# TopLevel.net
KiCad netlist of a schematic drawn in Altium Designer
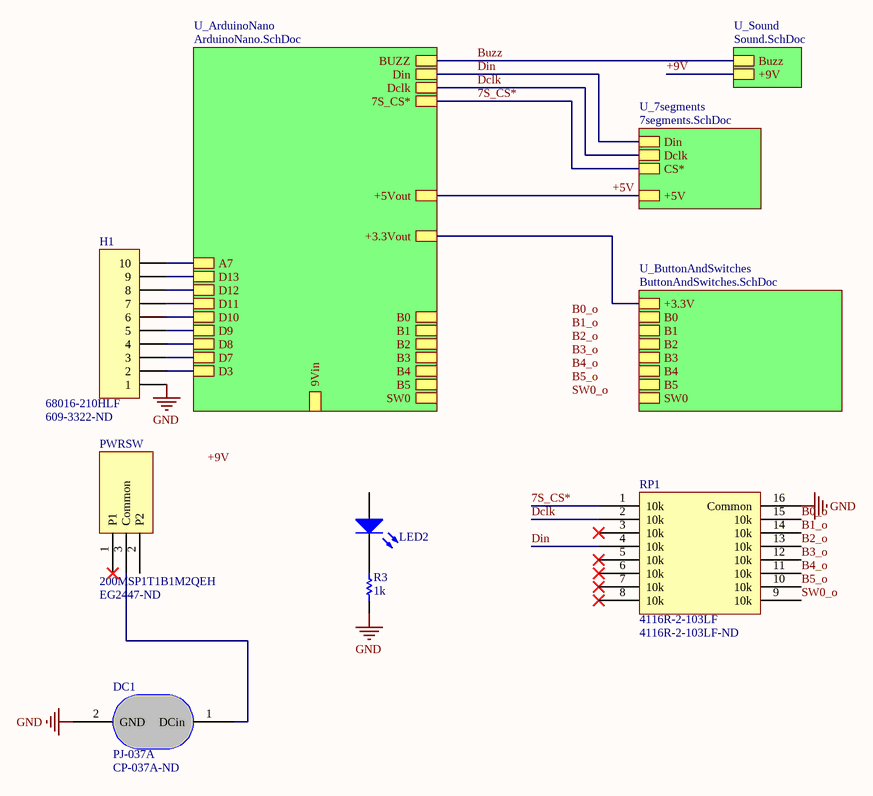
[diagram p0: TopLevel.SchDoc]

(export (version "E")
  (design (tool "Eeschema 10.0.6"))
  (components
    (comp (ref "DC1")
      (value "PJ-037A")
      (footprint "PJ-037A")
      (description "CONN PWR JACK 2X5.5MM SOLDER")
      (fields (field (name "SUPPLIER PART NUMBER 1") "CP-037A-ND"))
      (libsource (lib "ServoInterface") (part "DCpowerBarrel"))
    )
    (comp (ref "H1")
      (value "68016-210HLF")
      (footprint "Header1X10")
      (description "Header 10 Right Angle 100 mil")
      (fields
        (field (name "SUPPLIER PART NUMBER 1") "609-3322-ND")
        (field (name "PUBLISHER") "Altium Limited")
      )
      (libsource (lib "WarnickShareLibrary") (part "Header 10 Right Angle 100 mil"))
    )
    (comp (ref "LED2")
      (value "LTL-4223")
      (footprint "LED Through")
      (description "2 V drop 10 mA Red")
      (libsource (lib "ServoInterface") (part "LED_RED"))
    )
    (comp (ref "PWRSW")
      (value "200MSP1T1B1M2QEH")
      (footprint "200MSP1T1B1M2QEH")
      (description "SWITCH TOGGLE SPDT 3A 120V")
      (fields (field (name "SUPPLIER PART NUMBER 1") "EG2447-ND"))
      (libsource (lib "ServoInterface") (part "PowerSwitch"))
    )
    (comp (ref "R3")
      (value "1k")
      (footprint "Resistor Through Hole")
      (description "CF14JT1K00")
      (libsource (lib "ServoInterface") (part "Resistor_1k"))
    )
    (comp (ref "RP1")
      (value "4116R-2-103LF")
      (footprint "4100R")
      (fields (field (name "SUPPLIER PART NUMBER 1") "4116R-2-103LF-ND"))
      (libsource (lib "ServoInterface") (part "ResistorPack15"))
    )
  )
  (nets
    (net (code "4") (name "/7S_CS*") (class "Default")
      (node (ref "RP1") (pin "1") (pinfunction "10k_1") (pintype "passive"))
    )
    (net (code "6") (name "/A7") (class "Default")
      (node (ref "H1") (pin "10") (pinfunction "10_10") (pintype "passive"))
    )
    (net (code "9") (name "/B0_o") (class "Default")
      (node (ref "RP1") (pin "15") (pinfunction "10k_15") (pintype "passive"))
    )
    (net (code "12") (name "/B1_o") (class "Default")
      (node (ref "RP1") (pin "14") (pinfunction "10k_14") (pintype "passive"))
    )
    (net (code "15") (name "/B2_o") (class "Default")
      (node (ref "RP1") (pin "13") (pinfunction "10k_13") (pintype "passive"))
    )
    (net (code "18") (name "/B3_o") (class "Default")
      (node (ref "RP1") (pin "12") (pinfunction "10k_12") (pintype "passive"))
    )
    (net (code "21") (name "/B4_o") (class "Default")
      (node (ref "RP1") (pin "11") (pinfunction "10k_11") (pintype "passive"))
    )
    (net (code "24") (name "/B5_o") (class "Default")
      (node (ref "RP1") (pin "10") (pinfunction "10k_10") (pintype "passive"))
    )
    (net (code "26") (name "/D3") (class "Default")
      (node (ref "H1") (pin "2") (pinfunction "2_2") (pintype "passive"))
    )
    (net (code "27") (name "/D7") (class "Default")
      (node (ref "H1") (pin "3") (pinfunction "3_3") (pintype "passive"))
    )
    (net (code "28") (name "/D8") (class "Default")
      (node (ref "H1") (pin "4") (pinfunction "4_4") (pintype "passive"))
    )
    (net (code "29") (name "/D9") (class "Default")
      (node (ref "H1") (pin "5") (pinfunction "5_5") (pintype "passive"))
    )
    (net (code "30") (name "/D10") (class "Default")
      (node (ref "H1") (pin "6") (pinfunction "6_6") (pintype "passive"))
    )
    (net (code "31") (name "/D11") (class "Default")
      (node (ref "H1") (pin "7") (pinfunction "7_7") (pintype "passive"))
    )
    (net (code "32") (name "/D12") (class "Default")
      (node (ref "H1") (pin "8") (pinfunction "8_8") (pintype "passive"))
    )
    (net (code "33") (name "/D13") (class "Default")
      (node (ref "H1") (pin "9") (pinfunction "9_9") (pintype "passive"))
    )
    (net (code "34") (name "/Dclk") (class "Default")
      (node (ref "RP1") (pin "2") (pinfunction "10k_2") (pintype "passive"))
    )
    (net (code "35") (name "/Din") (class "Default")
      (node (ref "RP1") (pin "4") (pinfunction "10k_4") (pintype "passive"))
    )
    (net (code "38") (name "/SW0_o") (class "Default")
      (node (ref "RP1") (pin "9") (pinfunction "10k_9") (pintype "passive"))
    )
    (net (code "39") (name "GND") (class "Default")
      (node (ref "DC1") (pin "2") (pinfunction "GND_2") (pintype "passive"))
      (node (ref "H1") (pin "1") (pinfunction "1_1") (pintype "passive"))
      (node (ref "R3") (pin "2") (pinfunction "2_2") (pintype "passive"))
      (node (ref "RP1") (pin "16") (pinfunction "Common_16") (pintype "passive"))
    )
    (net (code "40") (name "Net-(DC1-DCin)") (class "Default")
      (node (ref "DC1") (pin "1") (pinfunction "DCin_1") (pintype "passive"))
      (node (ref "PWRSW") (pin "3") (pinfunction "Common_3") (pintype "passive"))
    )
    (net (code "41") (name "Net-(LED2-K)") (class "Default")
      (node (ref "LED2") (pin "2") (pinfunction "K_2") (pintype "passive"))
      (node (ref "R3") (pin "1") (pinfunction "1_1") (pintype "passive"))
    )
    (net (code "42") (name "unconnected-(LED2-A-Pad1)") (class "Default")
      (node (ref "LED2") (pin "1") (pinfunction "A_1") (pintype "passive"))
    )
    (net (code "43") (name "unconnected-(PWRSW-P1-Pad1)") (class "Default")
      (node (ref "PWRSW") (pin "1") (pinfunction "P1_1") (pintype "passive+no_connect"))
    )
    (net (code "44") (name "unconnected-(PWRSW-P2-Pad2)") (class "Default")
      (node (ref "PWRSW") (pin "2") (pinfunction "P2_2") (pintype "passive"))
    )
    (net (code "45") (name "unconnected-(RP1-10k-Pad3)") (class "Default")
      (node (ref "RP1") (pin "3") (pinfunction "10k_3") (pintype "passive+no_connect"))
    )
    (net (code "46") (name "unconnected-(RP1-10k-Pad5)") (class "Default")
      (node (ref "RP1") (pin "5") (pinfunction "10k_5") (pintype "passive+no_connect"))
    )
    (net (code "47") (name "unconnected-(RP1-10k-Pad6)") (class "Default")
      (node (ref "RP1") (pin "6") (pinfunction "10k_6") (pintype "passive+no_connect"))
    )
    (net (code "48") (name "unconnected-(RP1-10k-Pad7)") (class "Default")
      (node (ref "RP1") (pin "7") (pinfunction "10k_7") (pintype "passive+no_connect"))
    )
    (net (code "49") (name "unconnected-(RP1-10k-Pad8)") (class "Default")
      (node (ref "RP1") (pin "8") (pinfunction "10k_8") (pintype "passive+no_connect"))
    )
  )
)
